# mixer.net
KiCad netlist of a schematic drawn in Altium Designer
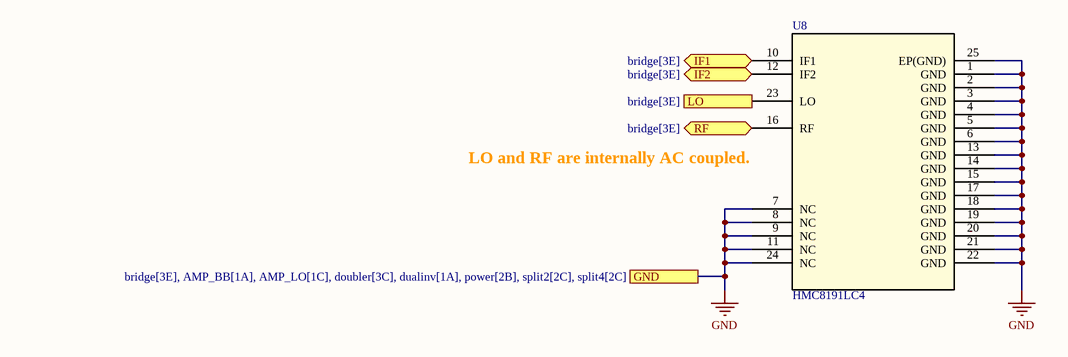
[diagram p0: mixer.SchDoc]

(export (version "E")
  (design (tool "Eeschema 10.0.6"))
  (components
    (comp (ref "U8")
      (value "HMC8191LC4")
      (footprint "HMC8191_E-24-1")
      (description "6 GHz to 26.5 GHz,\r\nWideband I/Q Mixer")
      (fields (field (name "MANUFACTURER") "Analog Devices"))
      (libsource (lib "FullyDigital") (part "HMC8191LC4"))
    )
  )
  (nets
    (net (code "1") (name "/IF1") (class "Default")
      (node (ref "U8") (pin "10") (pinfunction "IF1_10") (pintype "passive"))
    )
    (net (code "2") (name "/IF2") (class "Default")
      (node (ref "U8") (pin "12") (pinfunction "IF2_12") (pintype "passive"))
    )
    (net (code "3") (name "/LO") (class "Default")
      (node (ref "U8") (pin "23") (pinfunction "LO_23") (pintype "passive"))
    )
    (net (code "4") (name "/RF") (class "Default")
      (node (ref "U8") (pin "16") (pinfunction "RF_16") (pintype "passive"))
    )
    (net (code "5") (name "GND") (class "Default")
      (node (ref "U8") (pin "1") (pinfunction "GND_1") (pintype "passive"))
      (node (ref "U8") (pin "11") (pinfunction "NC_11") (pintype "passive"))
      (node (ref "U8") (pin "13") (pinfunction "GND_13") (pintype "passive"))
      (node (ref "U8") (pin "14") (pinfunction "GND_14") (pintype "passive"))
      (node (ref "U8") (pin "15") (pinfunction "GND_15") (pintype "passive"))
      (node (ref "U8") (pin "17") (pinfunction "GND_17") (pintype "passive"))
      (node (ref "U8") (pin "18") (pinfunction "GND_18") (pintype "passive"))
      (node (ref "U8") (pin "19") (pinfunction "GND_19") (pintype "passive"))
      (node (ref "U8") (pin "2") (pinfunction "GND_2") (pintype "passive"))
      (node (ref "U8") (pin "20") (pinfunction "GND_20") (pintype "passive"))
      (node (ref "U8") (pin "21") (pinfunction "GND_21") (pintype "passive"))
      (node (ref "U8") (pin "22") (pinfunction "GND_22") (pintype "passive"))
      (node (ref "U8") (pin "24") (pinfunction "NC_24") (pintype "passive"))
      (node (ref "U8") (pin "25") (pinfunction "EP(GND)_25") (pintype "passive"))
      (node (ref "U8") (pin "3") (pinfunction "GND_3") (pintype "passive"))
      (node (ref "U8") (pin "4") (pinfunction "GND_4") (pintype "passive"))
      (node (ref "U8") (pin "5") (pinfunction "GND_5") (pintype "passive"))
      (node (ref "U8") (pin "6") (pinfunction "GND_6") (pintype "passive"))
      (node (ref "U8") (pin "7") (pinfunction "NC_7") (pintype "passive"))
      (node (ref "U8") (pin "8") (pinfunction "NC_8") (pintype "passive"))
      (node (ref "U8") (pin "9") (pinfunction "NC_9") (pintype "passive"))
    )
  )
)
